# USB.net
KiCad netlist of a schematic drawn in Altium Designer
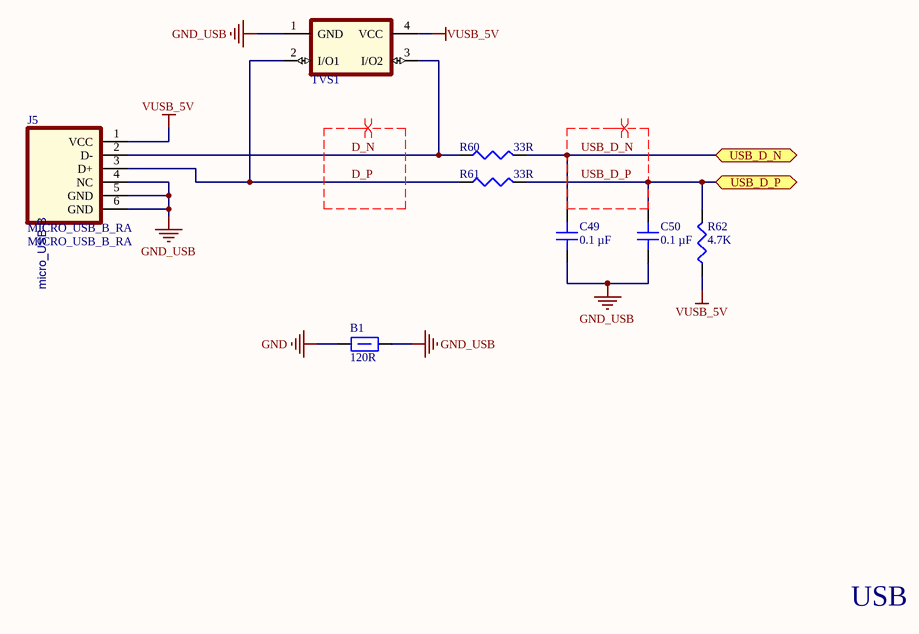
[diagram p0: USB.SchDoc]

(export (version "E")
  (design (tool "Eeschema 10.0.6"))
  (components
    (comp (ref "B1")
      (value "120R")
      (footprint "F0603")
      (description "BEAD FERRITE 120R 1LN SMD 0603")
      (fields (field (name "MANUFACTURER") "MURATA"))
      (libsource (lib "FILTER_LIB") (part "BEAD FERRITE 120R 1LN SMD 0603"))
    )
    (comp (ref "C49")
      (value "0.1 µF")
      (footprint "CAP 0603_1608")
      (description "CAP CER 0.1UF 50V X7R 0603")
      (fields (field (name "PART NUMBER") "0603BB104K500NGT"))
      (libsource (lib "Celestial Altium Library - altium_library") (part "Capacitor"))
    )
    (comp (ref "C50")
      (value "0.1 µF")
      (footprint "CAP 0603_1608")
      (description "CAP CER 0.1UF 50V X7R 0603")
      (fields (field (name "PART NUMBER") "0603BB104K500NGT"))
      (libsource (lib "Celestial Altium Library - altium_library") (part "Capacitor"))
    )
    (comp (ref "J5")
      (value "MICRO_USB_B_RA")
      (footprint "MICRO_USB_B")
      (description "CONN MICRO B USB 2.0 RECEPTACLE 5POS SMD RA")
      (fields (field (name "MANUFACTURER") "AMPHENOL") (field (name "ALTIUM_VALUE") "MICRO_USB_B_RA"))
      (libsource (lib "CONNECTOR_LIB") (part "MICRO_USB_B_RA"))
    )
    (comp (ref "R60")
      (value "33R")
      (footprint "R 0603(1608)")
      (description "Res Thick Film 0603 33 Ohm 1% 1/10W +/-100ppm/ßC Molded SMD Paper T/R")
      (fields
        (field (name "MANUFACTURER") "Yageo")
        (field (name "MANUFACTURER PART NUMBER") "RC0603FR-0733RL")
      )
      (libsource (lib "Miscellaneous Devices") (part "Res3"))
    )
    (comp (ref "R61")
      (value "33R")
      (footprint "R 0603(1608)")
      (description "Res Thick Film 0603 33 Ohm 1% 1/10W +/-100ppm/ßC Molded SMD Paper T/R")
      (fields
        (field (name "MANUFACTURER") "Yageo")
        (field (name "MANUFACTURER PART NUMBER") "RC0603FR-0733RL")
      )
      (libsource (lib "Miscellaneous Devices") (part "Res3"))
    )
    (comp (ref "R62")
      (value "4.7K")
      (footprint "R 0603(1608)")
      (description "Res Thick Film 0603 4.7K Ohm 5% 0.1W(1/10W) ±100ppm/C Molded SMD Paper T/R")
      (fields
        (field (name "MANUFACTURER") "Yageo")
        (field (name "MANUFACTURER PART NUMBER") "RC0603JR-074K7L")
      )
      (libsource (lib "Miscellaneous Devices") (part "Res3"))
    )
    (comp (ref "TVS1")
      (value "TVS DIODE PRTR5V0U2X,215 5.5VWM 6V SOT143")
      (footprint "SOT143")
      (fields (field (name "MANUFACTURER") "NXP SEMI"))
      (libsource (lib "DISCRETE_LIB") (part "TVS DIODE PRTR5V0U2X,215 5.5VWM 6V SOT143"))
    )
  )
  (nets
    (net (code "1") (name "/D_N") (class "Default")
      (node (ref "J5") (pin "2") (pinfunction "D-_2") (pintype "passive"))
      (node (ref "R60") (pin "2") (pinfunction "2_2") (pintype "passive"))
      (node (ref "TVS1") (pin "3") (pinfunction "I/O2_3") (pintype "bidirectional"))
    )
    (net (code "2") (name "/D_P") (class "Default")
      (node (ref "J5") (pin "3") (pinfunction "D+_3") (pintype "passive"))
      (node (ref "R61") (pin "2") (pinfunction "2_2") (pintype "passive"))
      (node (ref "TVS1") (pin "2") (pinfunction "I/O1_2") (pintype "bidirectional"))
    )
    (net (code "3") (name "/USB_D_N") (class "Default")
      (node (ref "C49") (pin "2") (pinfunction "2_2") (pintype "passive"))
      (node (ref "R60") (pin "1") (pinfunction "1_1") (pintype "passive"))
    )
    (net (code "4") (name "/USB_D_P") (class "Default")
      (node (ref "C50") (pin "2") (pinfunction "2_2") (pintype "passive"))
      (node (ref "R61") (pin "1") (pinfunction "1_1") (pintype "passive"))
      (node (ref "R62") (pin "1") (pinfunction "1_1") (pintype "passive"))
    )
    (net (code "5") (name "GND") (class "Default")
      (node (ref "B1") (pin "1") (pinfunction "1_1") (pintype "passive"))
    )
    (net (code "6") (name "GND_USB") (class "Default")
      (node (ref "B1") (pin "2") (pinfunction "2_2") (pintype "passive"))
      (node (ref "C49") (pin "1") (pinfunction "1_1") (pintype "passive"))
      (node (ref "C50") (pin "1") (pinfunction "1_1") (pintype "passive"))
      (node (ref "J5") (pin "4") (pinfunction "NC_4") (pintype "passive"))
      (node (ref "J5") (pin "5") (pinfunction "GND_5") (pintype "passive"))
      (node (ref "J5") (pin "6") (pinfunction "GND_6") (pintype "passive"))
      (node (ref "TVS1") (pin "1") (pinfunction "GND_1") (pintype "power_in"))
    )
    (net (code "7") (name "VUSB_5V") (class "Default")
      (node (ref "J5") (pin "1") (pinfunction "VCC_1") (pintype "passive"))
      (node (ref "R62") (pin "2") (pinfunction "2_2") (pintype "passive"))
      (node (ref "TVS1") (pin "4") (pinfunction "VCC_4") (pintype "power_in"))
    )
  )
)
